# Roby-Eva.net
KiCad netlist of a schematic drawn in Altium Designer
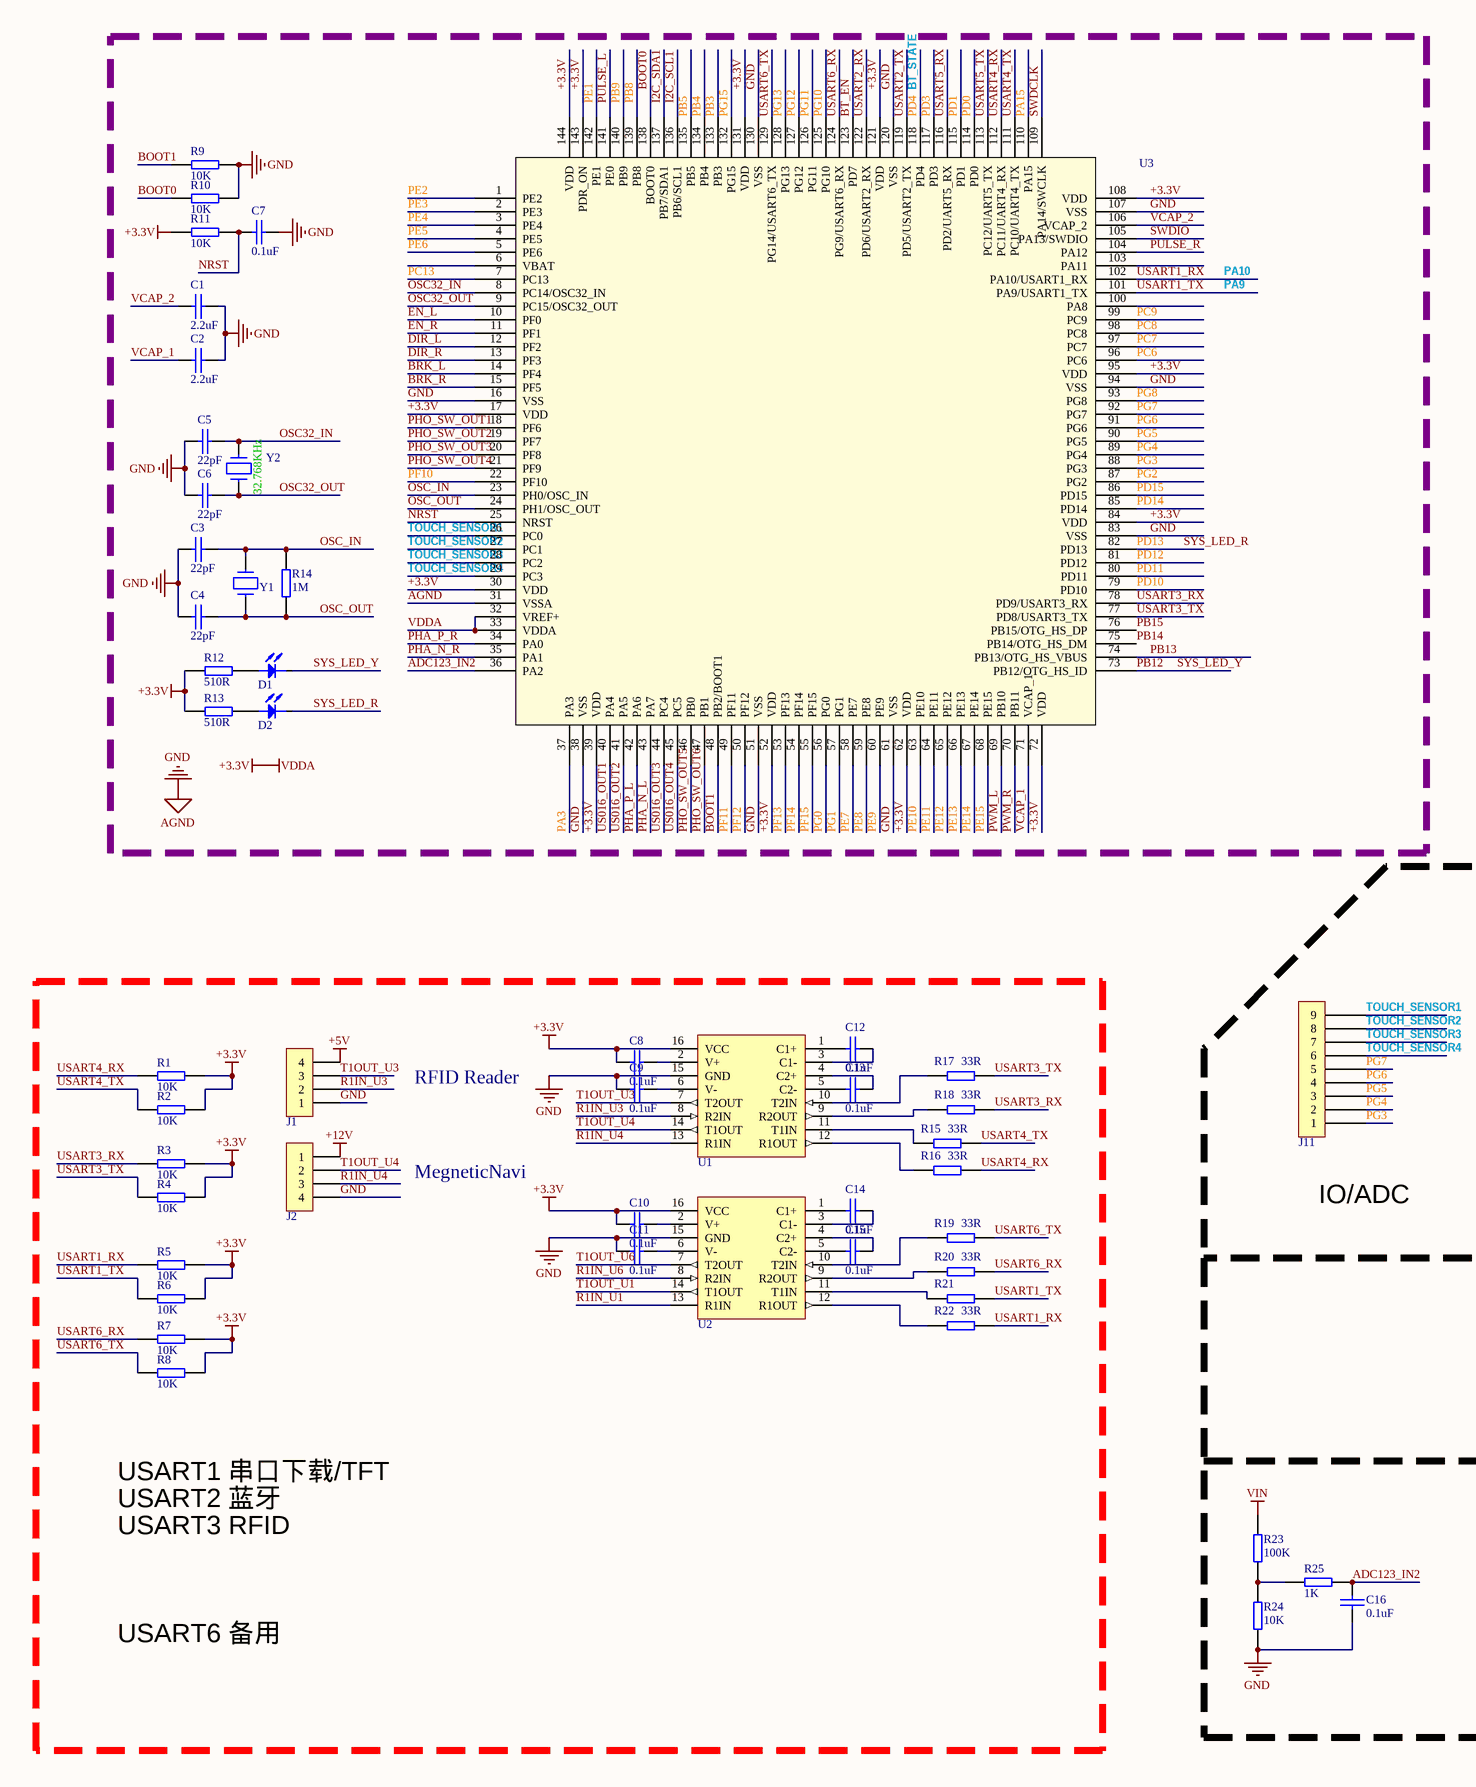
[diagram p0: Roby-Eva.SchDoc, left]
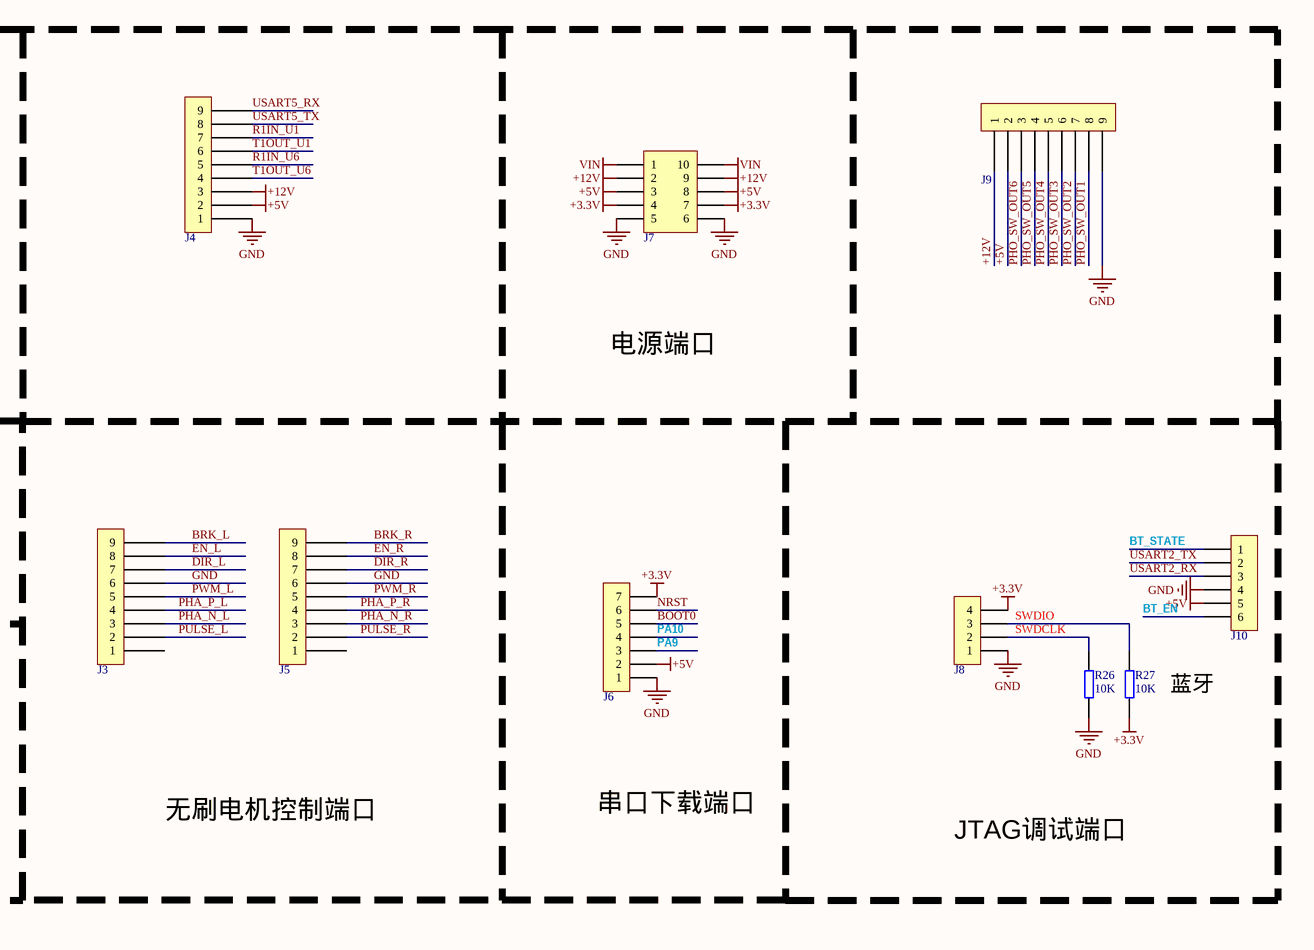
[diagram p1: Roby-Eva.SchDoc, right]

(export (version "E")
  (design (tool "Eeschema 10.0.6"))
  (components
    (comp (ref "C1")
      (value "贴片电容0805")
      (footprint "0805C")
      (fields (field (name "ALTIUM_UNNAMED_1") "2.2uF"))
      (libsource (lib "Integrated_Library") (part "贴片电容0805"))
    )
    (comp (ref "C2")
      (value "贴片电容0805")
      (footprint "0805C")
      (fields (field (name "ALTIUM_UNNAMED_1") "2.2uF"))
      (libsource (lib "Integrated_Library") (part "贴片电容0805"))
    )
    (comp (ref "C3")
      (value "贴片电容0805")
      (footprint "0805C")
      (fields (field (name "ALTIUM_UNNAMED_1") "22pF"))
      (libsource (lib "Integrated_Library") (part "贴片电容0805"))
    )
    (comp (ref "C4")
      (value "贴片电容0805")
      (footprint "0805C")
      (fields (field (name "ALTIUM_UNNAMED_1") "22pF"))
      (libsource (lib "Integrated_Library") (part "贴片电容0805"))
    )
    (comp (ref "C5")
      (value "贴片电容0805")
      (footprint "0805C")
      (fields (field (name "ALTIUM_UNNAMED_1") "22pF"))
      (libsource (lib "Integrated_Library") (part "贴片电容0805"))
    )
    (comp (ref "C6")
      (value "贴片电容0805")
      (footprint "0805C")
      (fields (field (name "ALTIUM_UNNAMED_1") "22pF"))
      (libsource (lib "Integrated_Library") (part "贴片电容0805"))
    )
    (comp (ref "C7")
      (value "贴片电容0805")
      (footprint "0805C")
      (fields (field (name "ALTIUM_UNNAMED_1") "0.1uF"))
      (libsource (lib "Integrated_Library") (part "贴片电容0805"))
    )
    (comp (ref "C8")
      (value "贴片电容0805")
      (footprint "0805C")
      (fields (field (name "ALTIUM_UNNAMED_1") "0.1uF"))
      (libsource (lib "Integrated_Library") (part "贴片电容0805"))
    )
    (comp (ref "C9")
      (value "贴片电容0805")
      (footprint "0805C")
      (fields (field (name "ALTIUM_UNNAMED_1") "0.1uF"))
      (libsource (lib "Integrated_Library") (part "贴片电容0805"))
    )
    (comp (ref "C10")
      (value "贴片电容0805")
      (footprint "0805C")
      (fields (field (name "ALTIUM_UNNAMED_1") "0.1uF"))
      (libsource (lib "Integrated_Library") (part "贴片电容0805"))
    )
    (comp (ref "C11")
      (value "贴片电容0805")
      (footprint "0805C")
      (fields (field (name "ALTIUM_UNNAMED_1") "0.1uF"))
      (libsource (lib "Integrated_Library") (part "贴片电容0805"))
    )
    (comp (ref "C12")
      (value "贴片电容0805")
      (footprint "0805C")
      (fields (field (name "ALTIUM_UNNAMED_1") "0.1uF"))
      (libsource (lib "Integrated_Library") (part "贴片电容0805"))
    )
    (comp (ref "C13")
      (value "贴片电容0805")
      (footprint "0805C")
      (fields (field (name "ALTIUM_UNNAMED_1") "0.1uF"))
      (libsource (lib "Integrated_Library") (part "贴片电容0805"))
    )
    (comp (ref "C14")
      (value "贴片电容0805")
      (footprint "0805C")
      (fields (field (name "ALTIUM_UNNAMED_1") "0.1uF"))
      (libsource (lib "Integrated_Library") (part "贴片电容0805"))
    )
    (comp (ref "C15")
      (value "贴片电容0805")
      (footprint "0805C")
      (fields (field (name "ALTIUM_UNNAMED_1") "0.1uF"))
      (libsource (lib "Integrated_Library") (part "贴片电容0805"))
    )
    (comp (ref "C16")
      (value "贴片电容0805")
      (footprint "0805C")
      (fields (field (name "ALTIUM_UNNAMED_1") "0.1uF"))
      (libsource (lib "Integrated_Library") (part "贴片电容0805"))
    )
    (comp (ref "D1")
      (value "LED_DIP")
      (footprint "LED_DIP")
      (libsource (lib "Integrated_Library") (part "LED_DIP"))
    )
    (comp (ref "D2")
      (value "LED_DIP")
      (footprint "LED_DIP")
      (libsource (lib "Integrated_Library") (part "LED_DIP"))
    )
    (comp (ref "J1")
      (value "XH2.54-4P-L")
      (footprint "XH2.54-4P-L")
      (libsource (lib "") (part "XH2.54-4P-L_1"))
    )
    (comp (ref "J2")
      (value "XH2.54-4P-L")
      (footprint "XH2.54-4P-L")
      (libsource (lib "Integrated_Library") (part "XH2.54-4P-L"))
    )
    (comp (ref "J3")
      (value "XH2.54-9P-L")
      (footprint "XH2.54-9P-L")
      (libsource (lib "") (part "XH2.54-9P-L_1"))
    )
    (comp (ref "J4")
      (value "XH2.54-9P-D")
      (footprint "XH2.54-9P-D")
      (libsource (lib "Integrated_Library") (part "XH2.54-9P-D"))
    )
    (comp (ref "J5")
      (value "XH2.54-9P-L")
      (footprint "XH2.54-9P-L")
      (libsource (lib "") (part "XH2.54-9P-L_1"))
    )
    (comp (ref "J6")
      (value "CON7")
      (footprint "HDR1X7H")
      (libsource (lib "Integrated_Library") (part "CON7"))
    )
    (comp (ref "J7")
      (value "CON 2x5")
      (footprint "CON 2X5")
      (libsource (lib "Integrated_Library") (part "CON 2x5"))
    )
    (comp (ref "J8")
      (value "CON4")
      (footprint "HDR1X4H")
      (libsource (lib "Integrated_Library") (part "CON4"))
    )
    (comp (ref "J9")
      (value "XH2.54-9P-L")
      (footprint "XH2.54-9P-L")
      (libsource (lib "Integrated_Library") (part "XH2.54-9P-L"))
    )
    (comp (ref "J10")
      (value "CON6")
      (footprint "HDR1X6H")
      (libsource (lib "Integrated_Library") (part "CON6"))
    )
    (comp (ref "J11")
      (value "XH2.54-9P-D")
      (footprint "XH2.54-9P-D")
      (libsource (lib "Integrated_Library") (part "XH2.54-9P-D"))
    )
    (comp (ref "R1")
      (value "贴片电阻0805")
      (footprint "0805R")
      (fields (field (name "ALTIUM_UNNAMED_1") "10K"))
      (libsource (lib "Integrated_Library") (part "贴片电阻0805"))
    )
    (comp (ref "R2")
      (value "贴片电阻0805")
      (footprint "0805R")
      (fields (field (name "ALTIUM_UNNAMED_1") "10K"))
      (libsource (lib "Integrated_Library") (part "贴片电阻0805"))
    )
    (comp (ref "R3")
      (value "贴片电阻0805")
      (footprint "0805R")
      (fields (field (name "ALTIUM_UNNAMED_1") "10K"))
      (libsource (lib "Integrated_Library") (part "贴片电阻0805"))
    )
    (comp (ref "R4")
      (value "贴片电阻0805")
      (footprint "0805R")
      (fields (field (name "ALTIUM_UNNAMED_1") "10K"))
      (libsource (lib "Integrated_Library") (part "贴片电阻0805"))
    )
    (comp (ref "R5")
      (value "贴片电阻0805")
      (footprint "0805R")
      (fields (field (name "ALTIUM_UNNAMED_1") "10K"))
      (libsource (lib "Integrated_Library") (part "贴片电阻0805"))
    )
    (comp (ref "R6")
      (value "贴片电阻0805")
      (footprint "0805R")
      (fields (field (name "ALTIUM_UNNAMED_1") "10K"))
      (libsource (lib "Integrated_Library") (part "贴片电阻0805"))
    )
    (comp (ref "R7")
      (value "贴片电阻0805")
      (footprint "0805R")
      (fields (field (name "ALTIUM_UNNAMED_1") "10K"))
      (libsource (lib "Integrated_Library") (part "贴片电阻0805"))
    )
    (comp (ref "R8")
      (value "贴片电阻0805")
      (footprint "0805R")
      (fields (field (name "ALTIUM_UNNAMED_1") "10K"))
      (libsource (lib "Integrated_Library") (part "贴片电阻0805"))
    )
    (comp (ref "R9")
      (value "贴片电阻0805")
      (footprint "0805R")
      (fields (field (name "ALTIUM_UNNAMED_1") "10K"))
      (libsource (lib "Integrated_Library") (part "贴片电阻0805"))
    )
    (comp (ref "R10")
      (value "贴片电阻0805")
      (footprint "0805R")
      (fields (field (name "ALTIUM_UNNAMED_1") "10K"))
      (libsource (lib "Integrated_Library") (part "贴片电阻0805"))
    )
    (comp (ref "R11")
      (value "贴片电阻0805")
      (footprint "0805R")
      (fields (field (name "ALTIUM_UNNAMED_1") "10K"))
      (libsource (lib "Integrated_Library") (part "贴片电阻0805"))
    )
    (comp (ref "R12")
      (value "贴片电阻0805")
      (footprint "0805R")
      (fields (field (name "ALTIUM_UNNAMED_1") "510R"))
      (libsource (lib "Integrated_Library") (part "贴片电阻0805"))
    )
    (comp (ref "R13")
      (value "贴片电阻0805")
      (footprint "0805R")
      (fields (field (name "ALTIUM_UNNAMED_1") "510R"))
      (libsource (lib "Integrated_Library") (part "贴片电阻0805"))
    )
    (comp (ref "R14")
      (value "贴片电阻0805")
      (footprint "0805R")
      (fields (field (name "ALTIUM_UNNAMED_1") "1M"))
      (libsource (lib "Integrated_Library") (part "贴片电阻0805"))
    )
    (comp (ref "R15")
      (value "贴片电阻0805")
      (footprint "0805R")
      (fields (field (name "ALTIUM_UNNAMED_1") "33R"))
      (libsource (lib "Integrated_Library") (part "贴片电阻0805"))
    )
    (comp (ref "R16")
      (value "贴片电阻0805")
      (footprint "0805R")
      (fields (field (name "ALTIUM_UNNAMED_1") "33R"))
      (libsource (lib "Integrated_Library") (part "贴片电阻0805"))
    )
    (comp (ref "R17")
      (value "贴片电阻0805")
      (footprint "0805R")
      (fields (field (name "ALTIUM_UNNAMED_1") "33R"))
      (libsource (lib "Integrated_Library") (part "贴片电阻0805"))
    )
    (comp (ref "R18")
      (value "贴片电阻0805")
      (footprint "0805R")
      (fields (field (name "ALTIUM_UNNAMED_1") "33R"))
      (libsource (lib "Integrated_Library") (part "贴片电阻0805"))
    )
    (comp (ref "R19")
      (value "贴片电阻0805")
      (footprint "0805R")
      (fields (field (name "ALTIUM_UNNAMED_1") "33R"))
      (libsource (lib "Integrated_Library") (part "贴片电阻0805"))
    )
    (comp (ref "R20")
      (value "贴片电阻0805")
      (footprint "0805R")
      (fields (field (name "ALTIUM_UNNAMED_1") "33R"))
      (libsource (lib "Integrated_Library") (part "贴片电阻0805"))
    )
    (comp (ref "R21")
      (value "贴片电阻0805")
      (footprint "0805R")
      (libsource (lib "Integrated_Library") (part "贴片电阻0805"))
    )
    (comp (ref "R22")
      (value "贴片电阻0805")
      (footprint "0805R")
      (fields (field (name "ALTIUM_UNNAMED_1") "33R"))
      (libsource (lib "Integrated_Library") (part "贴片电阻0805"))
    )
    (comp (ref "R23")
      (value "贴片电阻0805")
      (footprint "0805R")
      (fields (field (name "ALTIUM_UNNAMED_1") "100K"))
      (libsource (lib "Integrated_Library") (part "贴片电阻0805"))
    )
    (comp (ref "R24")
      (value "贴片电阻0805")
      (footprint "0805R")
      (fields (field (name "ALTIUM_UNNAMED_1") "10K"))
      (libsource (lib "Integrated_Library") (part "贴片电阻0805"))
    )
    (comp (ref "R25")
      (value "贴片电阻0805")
      (footprint "0805R")
      (fields (field (name "ALTIUM_UNNAMED_1") "1K"))
      (libsource (lib "Integrated_Library") (part "贴片电阻0805"))
    )
    (comp (ref "R26")
      (value "贴片电阻0805")
      (footprint "0805R")
      (fields (field (name "ALTIUM_UNNAMED_1") "10K"))
      (libsource (lib "Integrated_Library") (part "贴片电阻0805"))
    )
    (comp (ref "R27")
      (value "贴片电阻0805")
      (footprint "0805R")
      (fields (field (name "ALTIUM_UNNAMED_1") "10K"))
      (libsource (lib "Integrated_Library") (part "贴片电阻0805"))
    )
    (comp (ref "U1")
      (value "MAX232")
      (footprint "SOP16")
      (libsource (lib "Integrated_Library") (part "MAX232"))
    )
    (comp (ref "U2")
      (value "MAX232")
      (footprint "SOP16")
      (libsource (lib "Integrated_Library") (part "MAX232"))
    )
    (comp (ref "U3")
      (value "STM32F407")
      (footprint "LQFP144")
      (libsource (lib "Integrated_Library") (part "STM32F407"))
    )
    (comp (ref "Y1")
      (value "CRYSAL_SOP_2")
      (footprint "CRYSAL_SOP_2")
      (libsource (lib "Integrated_Library") (part "CRYSAL_SOP_2"))
    )
    (comp (ref "Y2")
      (value "CRYSAL_DIP_MINI")
      (footprint "CRYSAL_DIP_MINI")
      (libsource (lib "Integrated_Library") (part "CRYSAL_DIP_MINI"))
    )
  )
  (nets
    (net (code "1") (name "+3.3V") (class "Default")
      (node (ref "C10") (pin "2") (pinfunction "2_2") (pintype "passive"))
      (node (ref "C8") (pin "2") (pinfunction "2_2") (pintype "passive"))
      (node (ref "J6") (pin "7") (pinfunction "7_7") (pintype "passive"))
      (node (ref "J7") (pin "4") (pinfunction "4_4") (pintype "passive"))
      (node (ref "J7") (pin "7") (pinfunction "7_7") (pintype "passive"))
      (node (ref "J8") (pin "4") (pinfunction "4_4") (pintype "passive"))
      (node (ref "R1") (pin "2") (pinfunction "2_2") (pintype "passive"))
      (node (ref "R11") (pin "1") (pinfunction "1_1") (pintype "passive"))
      (node (ref "R12") (pin "1") (pinfunction "1_1") (pintype "passive"))
      (node (ref "R13") (pin "1") (pinfunction "1_1") (pintype "passive"))
      (node (ref "R2") (pin "2") (pinfunction "2_2") (pintype "passive"))
      (node (ref "R27") (pin "1") (pinfunction "1_1") (pintype "passive"))
      (node (ref "R3") (pin "2") (pinfunction "2_2") (pintype "passive"))
      (node (ref "R4") (pin "2") (pinfunction "2_2") (pintype "passive"))
      (node (ref "R5") (pin "2") (pinfunction "2_2") (pintype "passive"))
      (node (ref "R6") (pin "2") (pinfunction "2_2") (pintype "passive"))
      (node (ref "R7") (pin "2") (pinfunction "2_2") (pintype "passive"))
      (node (ref "R8") (pin "2") (pinfunction "2_2") (pintype "passive"))
      (node (ref "U1") (pin "16") (pinfunction "VCC_16") (pintype "power_in"))
      (node (ref "U2") (pin "16") (pinfunction "VCC_16") (pintype "power_in"))
      (node (ref "U3") (pin "108") (pinfunction "VDD_108") (pintype "passive"))
      (node (ref "U3") (pin "121") (pinfunction "VDD_121") (pintype "passive"))
      (node (ref "U3") (pin "131") (pinfunction "VDD_131") (pintype "passive"))
      (node (ref "U3") (pin "143") (pinfunction "PDR_ON_143") (pintype "passive"))
      (node (ref "U3") (pin "144") (pinfunction "VDD_144") (pintype "passive"))
      (node (ref "U3") (pin "17") (pinfunction "VDD_17") (pintype "passive"))
      (node (ref "U3") (pin "30") (pinfunction "VDD_30") (pintype "passive"))
      (node (ref "U3") (pin "32") (pinfunction "VREF+_32") (pintype "passive"))
      (node (ref "U3") (pin "33") (pinfunction "VDDA_33") (pintype "passive"))
      (node (ref "U3") (pin "39") (pinfunction "VDD_39") (pintype "passive"))
      (node (ref "U3") (pin "52") (pinfunction "VDD_52") (pintype "passive"))
      (node (ref "U3") (pin "62") (pinfunction "VDD_62") (pintype "passive"))
      (node (ref "U3") (pin "72") (pinfunction "VDD_72") (pintype "passive"))
      (node (ref "U3") (pin "84") (pinfunction "VDD_84") (pintype "passive"))
      (node (ref "U3") (pin "95") (pinfunction "VDD_95") (pintype "passive"))
    )
    (net (code "2") (name "+5V") (class "Default")
      (node (ref "J1") (pin "4") (pinfunction "4_4") (pintype "passive"))
      (node (ref "J10") (pin "5") (pinfunction "5_5") (pintype "passive"))
      (node (ref "J4") (pin "2") (pinfunction "2_2") (pintype "passive"))
      (node (ref "J6") (pin "2") (pinfunction "2_2") (pintype "passive"))
      (node (ref "J7") (pin "3") (pinfunction "3_3") (pintype "passive"))
      (node (ref "J7") (pin "8") (pinfunction "8_8") (pintype "passive"))
      (node (ref "J9") (pin "2") (pinfunction "2_2") (pintype "passive"))
    )
    (net (code "3") (name "+12V") (class "Default")
      (node (ref "J2") (pin "1") (pinfunction "1_1") (pintype "passive"))
      (node (ref "J4") (pin "3") (pinfunction "3_3") (pintype "passive"))
      (node (ref "J7") (pin "2") (pinfunction "2_2") (pintype "passive"))
      (node (ref "J7") (pin "9") (pinfunction "9_9") (pintype "passive"))
      (node (ref "J9") (pin "1") (pinfunction "1_1") (pintype "passive"))
    )
    (net (code "4") (name "/ADC123_IN2") (class "Default")
      (node (ref "C16") (pin "1") (pinfunction "1_1") (pintype "passive"))
      (node (ref "R25") (pin "2") (pinfunction "2_2") (pintype "passive"))
      (node (ref "U3") (pin "36") (pinfunction "PA2_36") (pintype "passive"))
    )
    (net (code "5") (name "/BOOT0") (class "Default")
      (node (ref "J6") (pin "5") (pinfunction "5_5") (pintype "passive"))
      (node (ref "R10") (pin "1") (pinfunction "1_1") (pintype "passive"))
      (node (ref "U3") (pin "138") (pinfunction "BOOT0_138") (pintype "passive"))
    )
    (net (code "6") (name "/BOOT1") (class "Default")
      (node (ref "R9") (pin "1") (pinfunction "1_1") (pintype "passive"))
      (node (ref "U3") (pin "48") (pinfunction "PB2/BOOT1_48") (pintype "passive"))
    )
    (net (code "7") (name "/BRK_L") (class "Default")
      (node (ref "J3") (pin "9") (pinfunction "9_9") (pintype "passive"))
      (node (ref "U3") (pin "14") (pinfunction "PF4_14") (pintype "passive"))
    )
    (net (code "8") (name "/BRK_R") (class "Default")
      (node (ref "J5") (pin "9") (pinfunction "9_9") (pintype "passive"))
      (node (ref "U3") (pin "15") (pinfunction "PF5_15") (pintype "passive"))
    )
    (net (code "9") (name "/BT_EN") (class "Default")
      (node (ref "J10") (pin "6") (pinfunction "6_6") (pintype "passive"))
      (node (ref "U3") (pin "123") (pinfunction "PD7_123") (pintype "passive"))
    )
    (net (code "10") (name "/BT_STATE") (class "Default")
      (node (ref "J10") (pin "1") (pinfunction "1_1") (pintype "passive"))
      (node (ref "U3") (pin "118") (pinfunction "PD4_118") (pintype "passive"))
    )
    (net (code "11") (name "/DIR_L") (class "Default")
      (node (ref "J3") (pin "7") (pinfunction "7_7") (pintype "passive"))
      (node (ref "U3") (pin "12") (pinfunction "PF2_12") (pintype "passive"))
    )
    (net (code "12") (name "/DIR_R") (class "Default")
      (node (ref "J5") (pin "7") (pinfunction "7_7") (pintype "passive"))
      (node (ref "U3") (pin "13") (pinfunction "PF3_13") (pintype "passive"))
    )
    (net (code "13") (name "/EN_L") (class "Default")
      (node (ref "J3") (pin "8") (pinfunction "8_8") (pintype "passive"))
      (node (ref "U3") (pin "10") (pinfunction "PF0_10") (pintype "passive"))
    )
    (net (code "14") (name "/EN_R") (class "Default")
      (node (ref "J5") (pin "8") (pinfunction "8_8") (pintype "passive"))
      (node (ref "U3") (pin "11") (pinfunction "PF1_11") (pintype "passive"))
    )
    (net (code "15") (name "/I2C_SCL1") (class "Default")
      (node (ref "U3") (pin "136") (pinfunction "PB6/SCL1_136") (pintype "passive"))
    )
    (net (code "16") (name "/I2C_SDA1") (class "Default")
      (node (ref "U3") (pin "137") (pinfunction "PB7/SDA1_137") (pintype "passive"))
    )
    (net (code "17") (name "/NRST") (class "Default")
      (node (ref "C7") (pin "2") (pinfunction "2_2") (pintype "passive"))
      (node (ref "J6") (pin "6") (pinfunction "6_6") (pintype "passive"))
      (node (ref "R11") (pin "2") (pinfunction "2_2") (pintype "passive"))
      (node (ref "U3") (pin "25") (pinfunction "NRST_25") (pintype "passive"))
    )
    (net (code "18") (name "/OSC32_IN") (class "Default")
      (node (ref "C5") (pin "1") (pinfunction "1_1") (pintype "passive"))
      (node (ref "U3") (pin "8") (pinfunction "PC14/OSC32_IN_8") (pintype "passive"))
      (node (ref "Y2") (pin "2") (pinfunction "2_2") (pintype "passive"))
    )
    (net (code "19") (name "/OSC32_OUT") (class "Default")
      (node (ref "C6") (pin "1") (pinfunction "1_1") (pintype "passive"))
      (node (ref "U3") (pin "9") (pinfunction "PC15/OSC32_OUT_9") (pintype "passive"))
      (node (ref "Y2") (pin "1") (pinfunction "1_1") (pintype "passive"))
    )
    (net (code "20") (name "/OSC_IN") (class "Default")
      (node (ref "C3") (pin "1") (pinfunction "1_1") (pintype "passive"))
      (node (ref "R14") (pin "2") (pinfunction "2_2") (pintype "passive"))
      (node (ref "U3") (pin "23") (pinfunction "PH0/OSC_IN_23") (pintype "passive"))
      (node (ref "Y1") (pin "2") (pinfunction "2_2") (pintype "passive"))
    )
    (net (code "21") (name "/OSC_OUT") (class "Default")
      (node (ref "C4") (pin "1") (pinfunction "1_1") (pintype "passive"))
      (node (ref "R14") (pin "1") (pinfunction "1_1") (pintype "passive"))
      (node (ref "U3") (pin "24") (pinfunction "PH1/OSC_OUT_24") (pintype "passive"))
      (node (ref "Y1") (pin "1") (pinfunction "1_1") (pintype "passive"))
    )
    (net (code "22") (name "/PA3") (class "Default")
      (node (ref "U3") (pin "37") (pinfunction "PA3_37") (pintype "passive"))
    )
    (net (code "23") (name "/PA9") (class "Default")
      (node (ref "J6") (pin "3") (pinfunction "3_3") (pintype "passive"))
      (node (ref "R21") (pin "2") (pinfunction "2_2") (pintype "passive"))
      (node (ref "R6") (pin "1") (pinfunction "1_1") (pintype "passive"))
      (node (ref "U3") (pin "101") (pinfunction "PA9/USART1_TX_101") (pintype "passive"))
    )
    (net (code "24") (name "/PA10") (class "Default")
      (node (ref "J6") (pin "4") (pinfunction "4_4") (pintype "passive"))
      (node (ref "R22") (pin "2") (pinfunction "2_2") (pintype "passive"))
      (node (ref "R5") (pin "1") (pinfunction "1_1") (pintype "passive"))
      (node (ref "U3") (pin "102") (pinfunction "PA10/USART1_RX_102") (pintype "passive"))
    )
    (net (code "25") (name "/PA15") (class "Default")
      (node (ref "U3") (pin "110") (pinfunction "PA15_110") (pintype "passive"))
    )
    (net (code "26") (name "/PB3") (class "Default")
      (node (ref "U3") (pin "133") (pinfunction "PB3_133") (pintype "passive"))
    )
    (net (code "27") (name "/PB4") (class "Default")
      (node (ref "U3") (pin "134") (pinfunction "PB4_134") (pintype "passive"))
    )
    (net (code "28") (name "/PB5") (class "Default")
      (node (ref "U3") (pin "135") (pinfunction "PB5_135") (pintype "passive"))
    )
    (net (code "29") (name "/PB8") (class "Default")
      (node (ref "U3") (pin "139") (pinfunction "PB8_139") (pintype "passive"))
    )
    (net (code "30") (name "/PB9") (class "Default")
      (node (ref "U3") (pin "140") (pinfunction "PB9_140") (pintype "passive"))
    )
    (net (code "31") (name "/PB12") (class "Default")
      (node (ref "D1") (pin "2") (pinfunction "2_2") (pintype "passive"))
      (node (ref "U3") (pin "73") (pinfunction "PB12/OTG_HS_ID_73") (pintype "passive"))
    )
    (net (code "32") (name "/PB13") (class "Default")
      (node (ref "U3") (pin "74") (pinfunction "PB13/OTG_HS_VBUS_74") (pintype "passive"))
    )
    (net (code "33") (name "/PB14") (class "Default")
      (node (ref "U3") (pin "75") (pinfunction "PB14/OTG_HS_DM_75") (pintype "passive"))
    )
    (net (code "34") (name "/PB15") (class "Default")
      (node (ref "U3") (pin "76") (pinfunction "PB15/OTG_HS_DP_76") (pintype "passive"))
    )
    (net (code "35") (name "/PC6") (class "Default")
      (node (ref "U3") (pin "96") (pinfunction "PC6_96") (pintype "passive"))
    )
    (net (code "36") (name "/PC7") (class "Default")
      (node (ref "U3") (pin "97") (pinfunction "PC7_97") (pintype "passive"))
    )
    (net (code "37") (name "/PC8") (class "Default")
      (node (ref "U3") (pin "98") (pinfunction "PC8_98") (pintype "passive"))
    )
    (net (code "38") (name "/PC9") (class "Default")
      (node (ref "U3") (pin "99") (pinfunction "PC9_99") (pintype "passive"))
    )
    (net (code "39") (name "/PC13") (class "Default")
      (node (ref "U3") (pin "7") (pinfunction "PC13_7") (pintype "passive"))
    )
    (net (code "40") (name "/PD0") (class "Default")
      (node (ref "U3") (pin "114") (pinfunction "PD0_114") (pintype "passive"))
    )
    (net (code "41") (name "/PD1") (class "Default")
      (node (ref "U3") (pin "115") (pinfunction "PD1_115") (pintype "passive"))
    )
    (net (code "42") (name "/PD3") (class "Default")
      (node (ref "U3") (pin "117") (pinfunction "PD3_117") (pintype "passive"))
    )
    (net (code "43") (name "/PD10") (class "Default")
      (node (ref "U3") (pin "79") (pinfunction "PD10_79") (pintype "passive"))
    )
    (net (code "44") (name "/PD11") (class "Default")
      (node (ref "U3") (pin "80") (pinfunction "PD11_80") (pintype "passive"))
    )
    (net (code "45") (name "/PD12") (class "Default")
      (node (ref "U3") (pin "81") (pinfunction "PD12_81") (pintype "passive"))
    )
    (net (code "46") (name "/PD13") (class "Default")
      (node (ref "D2") (pin "2") (pinfunction "2_2") (pintype "passive"))
      (node (ref "U3") (pin "82") (pinfunction "PD13_82") (pintype "passive"))
    )
    (net (code "47") (name "/PD14") (class "Default")
      (node (ref "U3") (pin "85") (pinfunction "PD14_85") (pintype "passive"))
    )
    (net (code "48") (name "/PD15") (class "Default")
      (node (ref "U3") (pin "86") (pinfunction "PD15_86") (pintype "passive"))
    )
    (net (code "49") (name "/PE1") (class "Default")
      (node (ref "U3") (pin "142") (pinfunction "PE1_142") (pintype "passive"))
    )
    (net (code "50") (name "/PE2") (class "Default")
      (node (ref "U3") (pin "1") (pinfunction "PE2_1") (pintype "passive"))
    )
    (net (code "51") (name "/PE3") (class "Default")
      (node (ref "U3") (pin "2") (pinfunction "PE3_2") (pintype "passive"))
    )
    (net (code "52") (name "/PE4") (class "Default")
      (node (ref "U3") (pin "3") (pinfunction "PE4_3") (pintype "passive"))
    )
    (net (code "53") (name "/PE5") (class "Default")
      (node (ref "U3") (pin "4") (pinfunction "PE5_4") (pintype "passive"))
    )
    (net (code "54") (name "/PE6") (class "Default")
      (node (ref "U3") (pin "5") (pinfunction "PE6_5") (pintype "passive"))
    )
    (net (code "55") (name "/PE7") (class "Default")
      (node (ref "U3") (pin "58") (pinfunction "PE7_58") (pintype "passive"))
    )
    (net (code "56") (name "/PE8") (class "Default")
      (node (ref "U3") (pin "59") (pinfunction "PE8_59") (pintype "passive"))
    )
    (net (code "57") (name "/PE9") (class "Default")
      (node (ref "U3") (pin "60") (pinfunction "PE9_60") (pintype "passive"))
    )
    (net (code "58") (name "/PE10") (class "Default")
      (node (ref "U3") (pin "63") (pinfunction "PE10_63") (pintype "passive"))
    )
    (net (code "59") (name "/PE11") (class "Default")
      (node (ref "U3") (pin "64") (pinfunction "PE11_64") (pintype "passive"))
    )
    (net (code "60") (name "/PE12") (class "Default")
      (node (ref "U3") (pin "65") (pinfunction "PE12_65") (pintype "passive"))
    )
    (net (code "61") (name "/PE13") (class "Default")
      (node (ref "U3") (pin "66") (pinfunction "PE13_66") (pintype "passive"))
    )
    (net (code "62") (name "/PE14") (class "Default")
      (node (ref "U3") (pin "67") (pinfunction "PE14_67") (pintype "passive"))
    )
    (net (code "63") (name "/PE15") (class "Default")
      (node (ref "U3") (pin "68") (pinfunction "PE15_68") (pintype "passive"))
    )
    (net (code "64") (name "/PF10") (class "Default")
      (node (ref "U3") (pin "22") (pinfunction "PF10_22") (pintype "passive"))
    )
    (net (code "65") (name "/PF11") (class "Default")
      (node (ref "U3") (pin "49") (pinfunction "PF11_49") (pintype "passive"))
    )
    (net (code "66") (name "/PF12") (class "Default")
      (node (ref "U3") (pin "50") (pinfunction "PF12_50") (pintype "passive"))
    )
    (net (code "67") (name "/PF13") (class "Default")
      (node (ref "U3") (pin "53") (pinfunction "PF13_53") (pintype "passive"))
    )
    (net (code "68") (name "/PF14") (class "Default")
      (node (ref "U3") (pin "54") (pinfunction "PF14_54") (pintype "passive"))
    )
    (net (code "69") (name "/PF15") (class "Default")
      (node (ref "U3") (pin "55") (pinfunction "PF15_55") (pintype "passive"))
    )
    (net (code "70") (name "/PG0") (class "Default")
      (node (ref "U3") (pin "56") (pinfunction "PG0_56") (pintype "passive"))
    )
    (net (code "71") (name "/PG1") (class "Default")
      (node (ref "U3") (pin "57") (pinfunction "PG1_57") (pintype "passive"))
    )
    (net (code "72") (name "/PG2") (class "Default")
      (node (ref "U3") (pin "87") (pinfunction "PG2_87") (pintype "passive"))
    )
    (net (code "73") (name "/PG3") (class "Default")
      (node (ref "J11") (pin "1") (pinfunction "1_1") (pintype "passive"))
      (node (ref "U3") (pin "88") (pinfunction "PG3_88") (pintype "passive"))
    )
    (net (code "74") (name "/PG4") (class "Default")
      (node (ref "J11") (pin "2") (pinfunction "2_2") (pintype "passive"))
      (node (ref "U3") (pin "89") (pinfunction "PG4_89") (pintype "passive"))
    )
    (net (code "75") (name "/PG5") (class "Default")
      (node (ref "J11") (pin "3") (pinfunction "3_3") (pintype "passive"))
      (node (ref "U3") (pin "90") (pinfunction "PG5_90") (pintype "passive"))
    )
    (net (code "76") (name "/PG6") (class "Default")
      (node (ref "J11") (pin "4") (pinfunction "4_4") (pintype "passive"))
      (node (ref "U3") (pin "91") (pinfunction "PG6_91") (pintype "passive"))
    )
    (net (code "77") (name "/PG7") (class "Default")
      (node (ref "J11") (pin "5") (pinfunction "5_5") (pintype "passive"))
      (node (ref "U3") (pin "92") (pinfunction "PG7_92") (pintype "passive"))
    )
    (net (code "78") (name "/PG8") (class "Default")
      (node (ref "U3") (pin "93") (pinfunction "PG8_93") (pintype "passive"))
    )
    (net (code "79") (name "/PG10") (class "Default")
      (node (ref "U3") (pin "125") (pinfunction "PG10_125") (pintype "passive"))
    )
    (net (code "80") (name "/PG11") (class "Default")
      (node (ref "U3") (pin "126") (pinfunction "PG11_126") (pintype "passive"))
    )
    (net (code "81") (name "/PG12") (class "Default")
      (node (ref "U3") (pin "127") (pinfunction "PG12_127") (pintype "passive"))
    )
    (net (code "82") (name "/PG13") (class "Default")
      (node (ref "U3") (pin "128") (pinfunction "PG13_128") (pintype "passive"))
    )
    (net (code "83") (name "/PG15") (class "Default")
      (node (ref "U3") (pin "132") (pinfunction "PG15_132") (pintype "passive"))
    )
    (net (code "84") (name "/PHA_N_L") (class "Default")
      (node (ref "J3") (pin "3") (pinfunction "3_3") (pintype "passive"))
      (node (ref "U3") (pin "43") (pinfunction "PA7_43") (pintype "passive"))
    )
    (net (code "85") (name "/PHA_N_R") (class "Default")
      (node (ref "J5") (pin "3") (pinfunction "3_3") (pintype "passive"))
      (node (ref "U3") (pin "35") (pinfunction "PA1_35") (pintype "passive"))
    )
    (net (code "86") (name "/PHA_P_L") (class "Default")
      (node (ref "J3") (pin "4") (pinfunction "4_4") (pintype "passive"))
      (node (ref "U3") (pin "42") (pinfunction "PA6_42") (pintype "passive"))
    )
    (net (code "87") (name "/PHA_P_R") (class "Default")
      (node (ref "J5") (pin "4") (pinfunction "4_4") (pintype "passive"))
      (node (ref "U3") (pin "34") (pinfunction "PA0_34") (pintype "passive"))
    )
    (net (code "88") (name "/PHO_SW_OUT1") (class "Default")
      (node (ref "J9") (pin "8") (pinfunction "8_8") (pintype "passive"))
      (node (ref "U3") (pin "18") (pinfunction "PF6_18") (pintype "passive"))
    )
    (net (code "89") (name "/PHO_SW_OUT2") (class "Default")
      (node (ref "J9") (pin "7") (pinfunction "7_7") (pintype "passive"))
      (node (ref "U3") (pin "19") (pinfunction "PF7_19") (pintype "passive"))
    )
    (net (code "90") (name "/PHO_SW_OUT3") (class "Default")
      (node (ref "J9") (pin "6") (pinfunction "6_6") (pintype "passive"))
      (node (ref "U3") (pin "20") (pinfunction "PF8_20") (pintype "passive"))
    )
    (net (code "91") (name "/PHO_SW_OUT4") (class "Default")
      (node (ref "J9") (pin "5") (pinfunction "5_5") (pintype "passive"))
      (node (ref "U3") (pin "21") (pinfunction "PF9_21") (pintype "passive"))
    )
    (net (code "92") (name "/PHO_SW_OUT5") (class "Default")
      (node (ref "J9") (pin "4") (pinfunction "4_4") (pintype "passive"))
      (node (ref "U3") (pin "46") (pinfunction "PB0_46") (pintype "passive"))
    )
    (net (code "93") (name "/PHO_SW_OUT6") (class "Default")
      (node (ref "J9") (pin "3") (pinfunction "3_3") (pintype "passive"))
      (node (ref "U3") (pin "47") (pinfunction "PB1_47") (pintype "passive"))
    )
    (net (code "94") (name "/PULSE_L") (class "Default")
      (node (ref "J3") (pin "2") (pinfunction "2_2") (pintype "passive"))
      (node (ref "U3") (pin "141") (pinfunction "PE0_141") (pintype "passive"))
    )
    (net (code "95") (name "/PULSE_R") (class "Default")
      (node (ref "J5") (pin "2") (pinfunction "2_2") (pintype "passive"))
      (node (ref "U3") (pin "104") (pinfunction "PA12_104") (pintype "passive"))
    )
    (net (code "96") (name "/PWM_L") (class "Default")
      (node (ref "J3") (pin "5") (pinfunction "5_5") (pintype "passive"))
      (node (ref "U3") (pin "69") (pinfunction "PB10_69") (pintype "passive"))
    )
    (net (code "97") (name "/PWM_R") (class "Default")
      (node (ref "J5") (pin "5") (pinfunction "5_5") (pintype "passive"))
      (node (ref "U3") (pin "70") (pinfunction "PB11_70") (pintype "passive"))
    )
    (net (code "98") (name "/R1IN_U1") (class "Default")
      (node (ref "J4") (pin "7") (pinfunction "7_7") (pintype "passive"))
      (node (ref "U2") (pin "13") (pinfunction "R1IN_13") (pintype "passive"))
    )
    (net (code "99") (name "/R1IN_U3") (class "Default")
      (node (ref "J1") (pin "2") (pinfunction "2_2") (pintype "passive"))
      (node (ref "U1") (pin "8") (pinfunction "R2IN_8") (pintype "input"))
    )
    (net (code "100") (name "/R1IN_U4") (class "Default")
      (node (ref "J2") (pin "3") (pinfunction "3_3") (pintype "passive"))
      (node (ref "U1") (pin "13") (pinfunction "R1IN_13") (pintype "passive"))
    )
    (net (code "101") (name "/R1IN_U6") (class "Default")
      (node (ref "J4") (pin "5") (pinfunction "5_5") (pintype "passive"))
      (node (ref "U2") (pin "8") (pinfunction "R2IN_8") (pintype "input"))
    )
    (net (code "102") (name "/SWDCLK") (class "Default")
      (node (ref "J8") (pin "2") (pinfunction "2_2") (pintype "passive"))
      (node (ref "R26") (pin "2") (pinfunction "2_2") (pintype "passive"))
      (node (ref "U3") (pin "109") (pinfunction "PA14/SWCLK_109") (pintype "passive"))
    )
    (net (code "103") (name "/SWDIO") (class "Default")
      (node (ref "J8") (pin "3") (pinfunction "3_3") (pintype "passive"))
      (node (ref "R27") (pin "2") (pinfunction "2_2") (pintype "passive"))
      (node (ref "U3") (pin "105") (pinfunction "PA13/SWDIO_105") (pintype "passive"))
    )
    (net (code "104") (name "/T1OUT_U1") (class "Default")
      (node (ref "J4") (pin "6") (pinfunction "6_6") (pintype "passive"))
      (node (ref "U2") (pin "14") (pinfunction "T1OUT_14") (pintype "output"))
    )
    (net (code "105") (name "/T1OUT_U3") (class "Default")
      (node (ref "J1") (pin "3") (pinfunction "3_3") (pintype "passive"))
      (node (ref "U1") (pin "7") (pinfunction "T2OUT_7") (pintype "output"))
    )
    (net (code "106") (name "/T1OUT_U4") (class "Default")
      (node (ref "J2") (pin "2") (pinfunction "2_2") (pintype "passive"))
      (node (ref "U1") (pin "14") (pinfunction "T1OUT_14") (pintype "output"))
    )
    (net (code "107") (name "/T1OUT_U6") (class "Default")
      (node (ref "J4") (pin "4") (pinfunction "4_4") (pintype "passive"))
      (node (ref "U2") (pin "7") (pinfunction "T2OUT_7") (pintype "output"))
    )
    (net (code "108") (name "/TOUCH_SENSOR1") (class "Default")
      (node (ref "J11") (pin "9") (pinfunction "9_9") (pintype "passive"))
      (node (ref "U3") (pin "26") (pinfunction "PC0_26") (pintype "passive"))
    )
    (net (code "109") (name "/TOUCH_SENSOR2") (class "Default")
      (node (ref "J11") (pin "8") (pinfunction "8_8") (pintype "passive"))
      (node (ref "U3") (pin "27") (pinfunction "PC1_27") (pintype "passive"))
    )
    (net (code "110") (name "/TOUCH_SENSOR3") (class "Default")
      (node (ref "J11") (pin "7") (pinfunction "7_7") (pintype "passive"))
      (node (ref "U3") (pin "28") (pinfunction "PC2_28") (pintype "passive"))
    )
    (net (code "111") (name "/TOUCH_SENSOR4") (class "Default")
      (node (ref "J11") (pin "6") (pinfunction "6_6") (pintype "passive"))
      (node (ref "U3") (pin "29") (pinfunction "PC3_29") (pintype "passive"))
    )
    (net (code "112") (name "/US016_OUT1") (class "Default")
      (node (ref "U3") (pin "40") (pinfunction "PA4_40") (pintype "passive"))
    )
    (net (code "113") (name "/US016_OUT2") (class "Default")
      (node (ref "U3") (pin "41") (pinfunction "PA5_41") (pintype "passive"))
    )
    (net (code "114") (name "/US016_OUT3") (class "Default")
      (node (ref "U3") (pin "44") (pinfunction "PC4_44") (pintype "passive"))
    )
    (net (code "115") (name "/US016_OUT4") (class "Default")
      (node (ref "U3") (pin "45") (pinfunction "PC5_45") (pintype "passive"))
    )
    (net (code "116") (name "/USART2_RX") (class "Default")
      (node (ref "J10") (pin "3") (pinfunction "3_3") (pintype "passive"))
      (node (ref "U3") (pin "122") (pinfunction "PD6/USART2_RX_122") (pintype "passive"))
    )
    (net (code "117") (name "/USART2_TX") (class "Default")
      (node (ref "J10") (pin "2") (pinfunction "2_2") (pintype "passive"))
      (node (ref "U3") (pin "119") (pinfunction "PD5/USART2_TX_119") (pintype "passive"))
    )
    (net (code "118") (name "/USART3_RX") (class "Default")
      (node (ref "R18") (pin "2") (pinfunction "2_2") (pintype "passive"))
      (node (ref "R3") (pin "1") (pinfunction "1_1") (pintype "passive"))
      (node (ref "U3") (pin "78") (pinfunction "PD9/USART3_RX_78") (pintype "passive"))
    )
    (net (code "119") (name "/USART3_TX") (class "Default")
      (node (ref "R17") (pin "2") (pinfunction "2_2") (pintype "passive"))
      (node (ref "R4") (pin "1") (pinfunction "1_1") (pintype "passive"))
      (node (ref "U3") (pin "77") (pinfunction "PD8/USART3_TX_77") (pintype "passive"))
    )
    (net (code "120") (name "/USART4_RX") (class "Default")
      (node (ref "R1") (pin "1") (pinfunction "1_1") (pintype "passive"))
      (node (ref "R16") (pin "2") (pinfunction "2_2") (pintype "passive"))
      (node (ref "U3") (pin "112") (pinfunction "PC11/UART4_RX_112") (pintype "passive"))
    )
    (net (code "121") (name "/USART4_TX") (class "Default")
      (node (ref "R15") (pin "2") (pinfunction "2_2") (pintype "passive"))
      (node (ref "R2") (pin "1") (pinfunction "1_1") (pintype "passive"))
      (node (ref "U3") (pin "111") (pinfunction "PC10/UART4_TX_111") (pintype "passive"))
    )
    (net (code "122") (name "/USART5_RX") (class "Default")
      (node (ref "J4") (pin "9") (pinfunction "9_9") (pintype "passive"))
      (node (ref "U3") (pin "116") (pinfunction "PD2/UART5_RX_116") (pintype "passive"))
    )
    (net (code "123") (name "/USART5_TX") (class "Default")
      (node (ref "J4") (pin "8") (pinfunction "8_8") (pintype "passive"))
      (node (ref "U3") (pin "113") (pinfunction "PC12/UART5_TX_113") (pintype "passive"))
    )
    (net (code "124") (name "/USART6_RX") (class "Default")
      (node (ref "R20") (pin "2") (pinfunction "2_2") (pintype "passive"))
      (node (ref "R7") (pin "1") (pinfunction "1_1") (pintype "passive"))
      (node (ref "U3") (pin "124") (pinfunction "PG9/USART6_RX_124") (pintype "passive"))
    )
    (net (code "125") (name "/USART6_TX") (class "Default")
      (node (ref "R19") (pin "2") (pinfunction "2_2") (pintype "passive"))
      (node (ref "R8") (pin "1") (pinfunction "1_1") (pintype "passive"))
      (node (ref "U3") (pin "129") (pinfunction "PG14/USART6_TX_129") (pintype "passive"))
    )
    (net (code "126") (name "/VCAP_1") (class "Default")
      (node (ref "C2") (pin "2") (pinfunction "2_2") (pintype "passive"))
      (node (ref "U3") (pin "71") (pinfunction "VCAP_1_71") (pintype "passive"))
    )
    (net (code "127") (name "/VCAP_2") (class "Default")
      (node (ref "C1") (pin "2") (pinfunction "2_2") (pintype "passive"))
      (node (ref "U3") (pin "106") (pinfunction "VCAP_2_106") (pintype "passive"))
    )
    (net (code "128") (name "AGND") (class "Default")
      (node (ref "C1") (pin "1") (pinfunction "1_1") (pintype "passive"))
      (node (ref "C11") (pin "2") (pinfunction "2_2") (pintype "passive"))
      (node (ref "C16") (pin "2") (pinfunction "2_2") (pintype "passive"))
      (node (ref "C2") (pin "1") (pinfunction "1_1") (pintype "passive"))
      (node (ref "C3") (pin "2") (pinfunction "2_2") (pintype "passive"))
      (node (ref "C4") (pin "2") (pinfunction "2_2") (pintype "passive"))
      (node (ref "C5") (pin "2") (pinfunction "2_2") (pintype "passive"))
      (node (ref "C6") (pin "2") (pinfunction "2_2") (pintype "passive"))
      (node (ref "C7") (pin "1") (pinfunction "1_1") (pintype "passive"))
      (node (ref "C9") (pin "2") (pinfunction "2_2") (pintype "passive"))
      (node (ref "J1") (pin "1") (pinfunction "1_1") (pintype "passive"))
      (node (ref "J10") (pin "4") (pinfunction "4_4") (pintype "passive"))
      (node (ref "J2") (pin "4") (pinfunction "4_4") (pintype "passive"))
      (node (ref "J3") (pin "6") (pinfunction "6_6") (pintype "passive"))
      (node (ref "J4") (pin "1") (pinfunction "1_1") (pintype "passive"))
      (node (ref "J5") (pin "6") (pinfunction "6_6") (pintype "passive"))
      (node (ref "J6") (pin "1") (pinfunction "1_1") (pintype "passive"))
      (node (ref "J7") (pin "5") (pinfunction "5_5") (pintype "passive"))
      (node (ref "J7") (pin "6") (pinfunction "6_6") (pintype "passive"))
      (node (ref "J8") (pin "1") (pinfunction "1_1") (pintype "passive"))
      (node (ref "J9") (pin "9") (pinfunction "9_9") (pintype "passive"))
      (node (ref "R10") (pin "2") (pinfunction "2_2") (pintype "passive"))
      (node (ref "R24") (pin "2") (pinfunction "2_2") (pintype "passive"))
      (node (ref "R26") (pin "1") (pinfunction "1_1") (pintype "passive"))
      (node (ref "R9") (pin "2") (pinfunction "2_2") (pintype "passive"))
      (node (ref "U1") (pin "15") (pinfunction "GND_15") (pintype "power_in"))
      (node (ref "U2") (pin "15") (pinfunction "GND_15") (pintype "power_in"))
      (node (ref "U3") (pin "107") (pinfunction "VSS_107") (pintype "passive"))
      (node (ref "U3") (pin "120") (pinfunction "VSS_120") (pintype "passive"))
      (node (ref "U3") (pin "130") (pinfunction "VSS_130") (pintype "passive"))
      (node (ref "U3") (pin "16") (pinfunction "VSS_16") (pintype "passive"))
      (node (ref "U3") (pin "31") (pinfunction "VSSA_31") (pintype "passive"))
      (node (ref "U3") (pin "38") (pinfunction "VSS_38") (pintype "passive"))
      (node (ref "U3") (pin "51") (pinfunction "VSS_51") (pintype "passive"))
      (node (ref "U3") (pin "61") (pinfunction "VSS_61") (pintype "passive"))
      (node (ref "U3") (pin "83") (pinfunction "VSS_83") (pintype "passive"))
      (node (ref "U3") (pin "94") (pinfunction "VSS_94") (pintype "passive"))
    )
    (net (code "129") (name "Net-(D1-Pad1)") (class "Default")
      (node (ref "D1") (pin "1") (pinfunction "1_1") (pintype "passive"))
      (node (ref "R12") (pin "2") (pinfunction "2_2") (pintype "passive"))
    )
    (net (code "130") (name "Net-(D2-Pad1)") (class "Default")
      (node (ref "D2") (pin "1") (pinfunction "1_1") (pintype "passive"))
      (node (ref "R13") (pin "2") (pinfunction "2_2") (pintype "passive"))
    )
    (net (code "131") (name "Net-(R23-Pad1)") (class "Default")
      (node (ref "R23") (pin "1") (pinfunction "1_1") (pintype "passive"))
      (node (ref "R24") (pin "1") (pinfunction "1_1") (pintype "passive"))
      (node (ref "R25") (pin "1") (pinfunction "1_1") (pintype "passive"))
    )
    (net (code "132") (name "Net-(U1-C1+)") (class "Default")
      (node (ref "C12") (pin "2") (pinfunction "2_2") (pintype "passive"))
      (node (ref "U1") (pin "1") (pinfunction "C1+_1") (pintype "passive"))
    )
    (net (code "133") (name "Net-(U1-C1-)") (class "Default")
      (node (ref "C12") (pin "1") (pinfunction "1_1") (pintype "passive"))
      (node (ref "U1") (pin "3") (pinfunction "C1-_3") (pintype "passive"))
    )
    (net (code "134") (name "Net-(U1-C2+)") (class "Default")
      (node (ref "C13") (pin "1") (pinfunction "1_1") (pintype "passive"))
      (node (ref "U1") (pin "4") (pinfunction "C2+_4") (pintype "passive"))
    )
    (net (code "135") (name "Net-(U1-C2-)") (class "Default")
      (node (ref "C13") (pin "2") (pinfunction "2_2") (pintype "passive"))
      (node (ref "U1") (pin "5") (pinfunction "C2-_5") (pintype "passive"))
    )
    (net (code "136") (name "Net-(U1-R1OUT)") (class "Default")
      (node (ref "R16") (pin "1") (pinfunction "1_1") (pintype "passive"))
      (node (ref "U1") (pin "12") (pinfunction "R1OUT_12") (pintype "output"))
    )
    (net (code "137") (name "Net-(U1-R2OUT)") (class "Default")
      (node (ref "R18") (pin "1") (pinfunction "1_1") (pintype "passive"))
      (node (ref "U1") (pin "9") (pinfunction "R2OUT_9") (pintype "output"))
    )
    (net (code "138") (name "Net-(U1-T1IN)") (class "Default")
      (node (ref "R15") (pin "1") (pinfunction "1_1") (pintype "passive"))
      (node (ref "U1") (pin "11") (pinfunction "T1IN_11") (pintype "passive"))
    )
    (net (code "139") (name "Net-(U1-T2IN)") (class "Default")
      (node (ref "R17") (pin "1") (pinfunction "1_1") (pintype "passive"))
      (node (ref "U1") (pin "10") (pinfunction "T2IN_10") (pintype "input"))
    )
    (net (code "140") (name "Net-(U1-V+)") (class "Default")
      (node (ref "C8") (pin "1") (pinfunction "1_1") (pintype "passive"))
      (node (ref "U1") (pin "2") (pinfunction "V+_2") (pintype "passive"))
    )
    (net (code "141") (name "Net-(U1-V-)") (class "Default")
      (node (ref "C9") (pin "1") (pinfunction "1_1") (pintype "passive"))
      (node (ref "U1") (pin "6") (pinfunction "V-_6") (pintype "passive"))
    )
    (net (code "142") (name "Net-(U2-C1+)") (class "Default")
      (node (ref "C14") (pin "2") (pinfunction "2_2") (pintype "passive"))
      (node (ref "U2") (pin "1") (pinfunction "C1+_1") (pintype "passive"))
    )
    (net (code "143") (name "Net-(U2-C1-)") (class "Default")
      (node (ref "C14") (pin "1") (pinfunction "1_1") (pintype "passive"))
      (node (ref "U2") (pin "3") (pinfunction "C1-_3") (pintype "passive"))
    )
    (net (code "144") (name "Net-(U2-C2+)") (class "Default")
      (node (ref "C15") (pin "1") (pinfunction "1_1") (pintype "passive"))
      (node (ref "U2") (pin "4") (pinfunction "C2+_4") (pintype "passive"))
    )
    (net (code "145") (name "Net-(U2-C2-)") (class "Default")
      (node (ref "C15") (pin "2") (pinfunction "2_2") (pintype "passive"))
      (node (ref "U2") (pin "5") (pinfunction "C2-_5") (pintype "passive"))
    )
    (net (code "146") (name "Net-(U2-R1OUT)") (class "Default")
      (node (ref "R22") (pin "1") (pinfunction "1_1") (pintype "passive"))
      (node (ref "U2") (pin "12") (pinfunction "R1OUT_12") (pintype "output"))
    )
    (net (code "147") (name "Net-(U2-R2OUT)") (class "Default")
      (node (ref "R20") (pin "1") (pinfunction "1_1") (pintype "passive"))
      (node (ref "U2") (pin "9") (pinfunction "R2OUT_9") (pintype "output"))
    )
    (net (code "148") (name "Net-(U2-T1IN)") (class "Default")
      (node (ref "R21") (pin "1") (pinfunction "1_1") (pintype "passive"))
      (node (ref "U2") (pin "11") (pinfunction "T1IN_11") (pintype "passive"))
    )
    (net (code "149") (name "Net-(U2-T2IN)") (class "Default")
      (node (ref "R19") (pin "1") (pinfunction "1_1") (pintype "passive"))
      (node (ref "U2") (pin "10") (pinfunction "T2IN_10") (pintype "input"))
    )
    (net (code "150") (name "Net-(U2-V+)") (class "Default")
      (node (ref "C10") (pin "1") (pinfunction "1_1") (pintype "passive"))
      (node (ref "U2") (pin "2") (pinfunction "V+_2") (pintype "passive"))
    )
    (net (code "151") (name "Net-(U2-V-)") (class "Default")
      (node (ref "C11") (pin "1") (pinfunction "1_1") (pintype "passive"))
      (node (ref "U2") (pin "6") (pinfunction "V-_6") (pintype "passive"))
    )
    (net (code "152") (name "VIN") (class "Default")
      (node (ref "J7") (pin "1") (pinfunction "1_1") (pintype "passive"))
      (node (ref "J7") (pin "10") (pinfunction "10_10") (pintype "passive"))
      (node (ref "R23") (pin "2") (pinfunction "2_2") (pintype "passive"))
    )
    (net (code "153") (name "unconnected-(J3-Pad1)") (class "Default")
      (node (ref "J3") (pin "1") (pinfunction "1_1") (pintype "passive"))
    )
    (net (code "154") (name "unconnected-(J5-Pad1)") (class "Default")
      (node (ref "J5") (pin "1") (pinfunction "1_1") (pintype "passive"))
    )
    (net (code "155") (name "unconnected-(U3-PA8-Pad100)") (class "Default")
      (node (ref "U3") (pin "100") (pinfunction "PA8_100") (pintype "passive"))
    )
    (net (code "156") (name "unconnected-(U3-PA11-Pad103)") (class "Default")
      (node (ref "U3") (pin "103") (pinfunction "PA11_103") (pintype "passive"))
    )
    (net (code "157") (name "unconnected-(U3-VBAT-Pad6)") (class "Default")
      (node (ref "U3") (pin "6") (pinfunction "VBAT_6") (pintype "passive"))
    )
  )
)
